# M224X.net
KiCad netlist of a schematic drawn in EAGLE
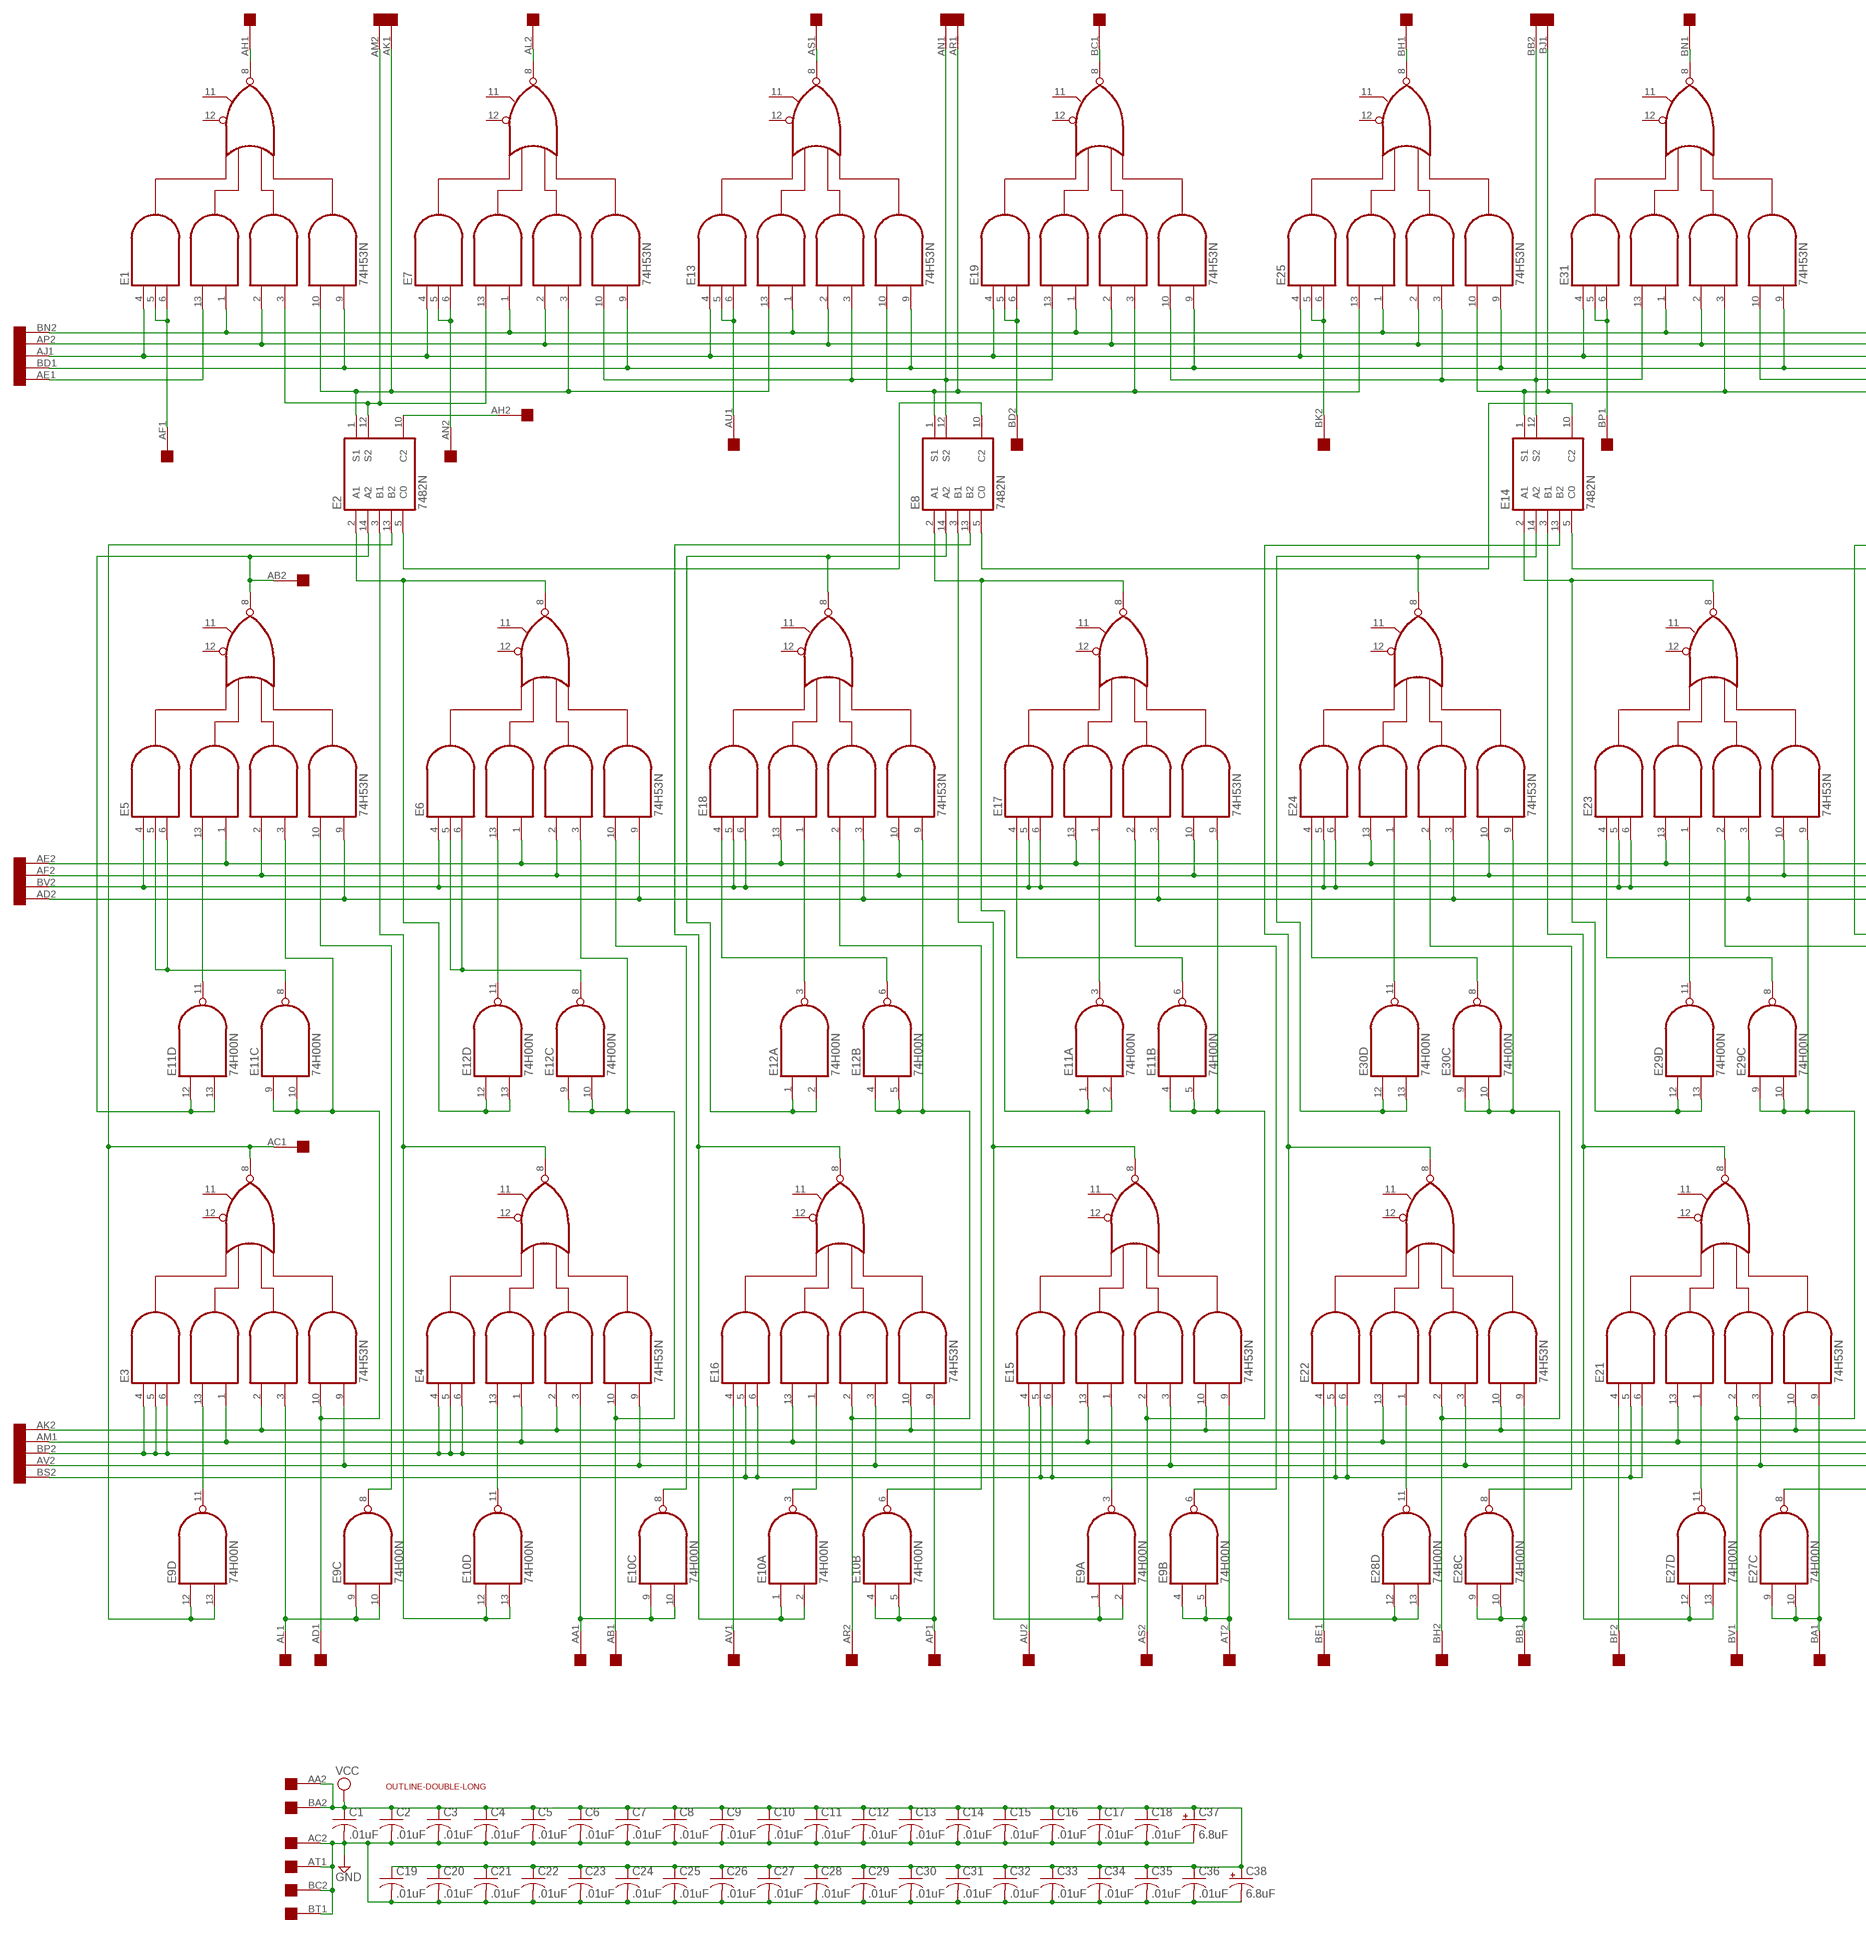
[diagram p0: schematic, sheet 1, part 1 of 2]
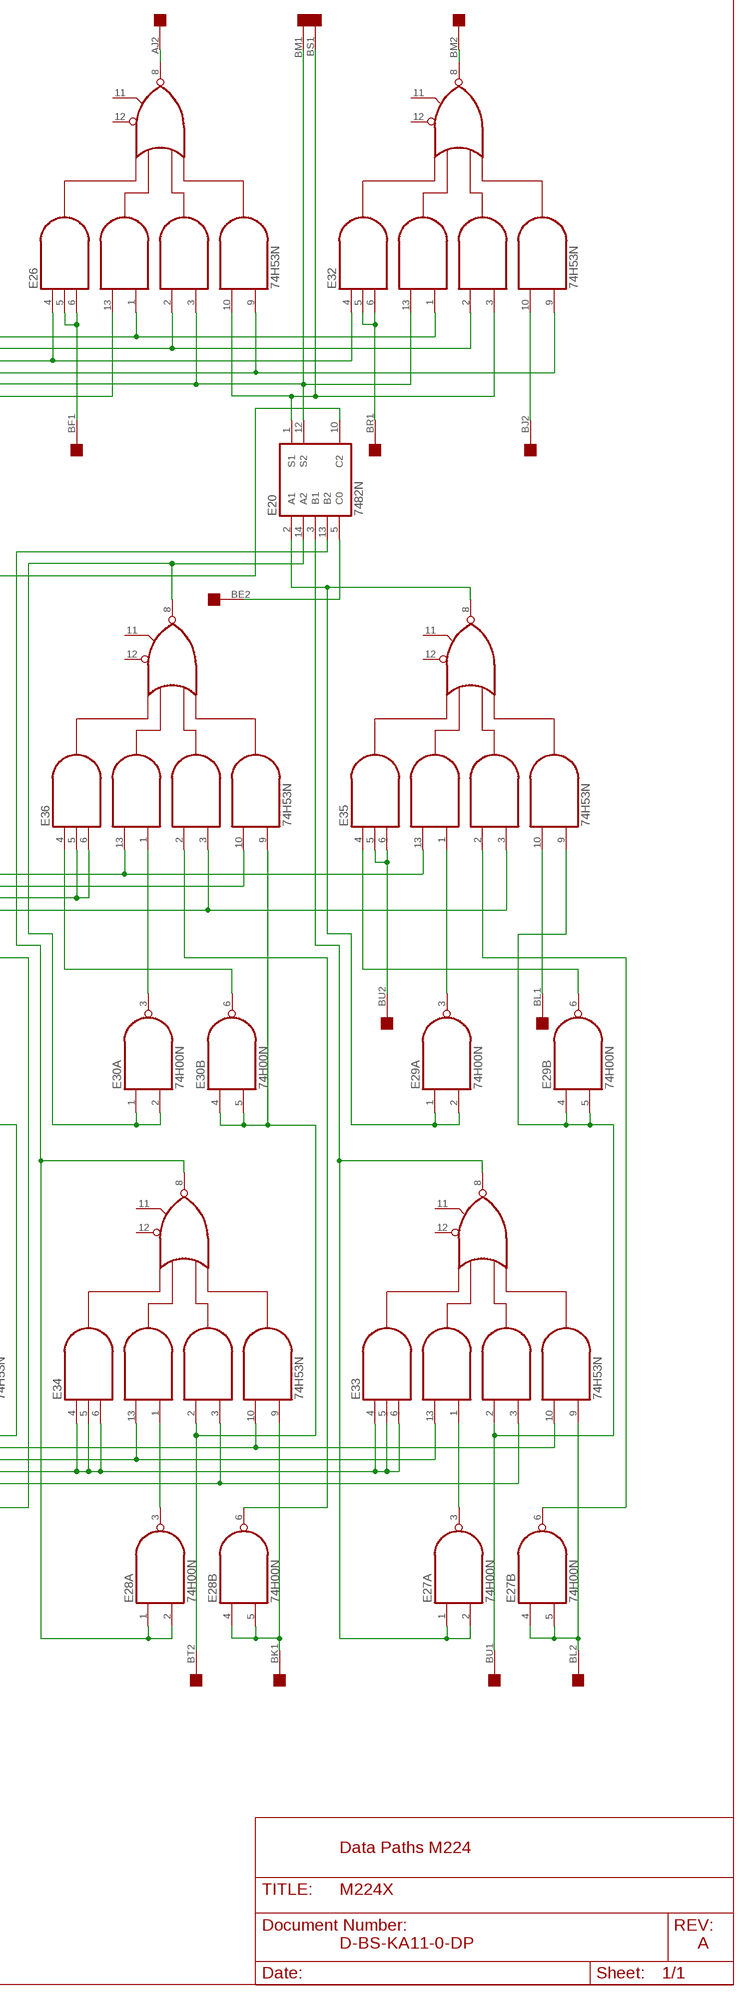
[diagram p1: schematic, sheet 1, part 2 of 2]

(export (version "E")
  (design (tool "Eeschema 10.0.6"))
  (components
    (comp (ref "C1")
      (value ".01uF")
      (footprint "eagle-import:C050-025X075")
      (libsource (lib "eagle-import") (part "C-US050-025X075"))
    )
    (comp (ref "C2")
      (value ".01uF")
      (footprint "eagle-import:C050-025X075")
      (libsource (lib "eagle-import") (part "C-US050-025X075"))
    )
    (comp (ref "C3")
      (value ".01uF")
      (footprint "eagle-import:C050-025X075")
      (libsource (lib "eagle-import") (part "C-US050-025X075"))
    )
    (comp (ref "C4")
      (value ".01uF")
      (footprint "eagle-import:C050-025X075")
      (libsource (lib "eagle-import") (part "C-US050-025X075"))
    )
    (comp (ref "C5")
      (value ".01uF")
      (footprint "eagle-import:C050-025X075")
      (libsource (lib "eagle-import") (part "C-US050-025X075"))
    )
    (comp (ref "C6")
      (value ".01uF")
      (footprint "eagle-import:C050-025X075")
      (libsource (lib "eagle-import") (part "C-US050-025X075"))
    )
    (comp (ref "C7")
      (value ".01uF")
      (footprint "eagle-import:C050-025X075")
      (libsource (lib "eagle-import") (part "C-US050-025X075"))
    )
    (comp (ref "C8")
      (value ".01uF")
      (footprint "eagle-import:C050-025X075")
      (libsource (lib "eagle-import") (part "C-US050-025X075"))
    )
    (comp (ref "C9")
      (value ".01uF")
      (footprint "eagle-import:C050-025X075")
      (libsource (lib "eagle-import") (part "C-US050-025X075"))
    )
    (comp (ref "C10")
      (value ".01uF")
      (footprint "eagle-import:C050-025X075")
      (libsource (lib "eagle-import") (part "C-US050-025X075"))
    )
    (comp (ref "C11")
      (value ".01uF")
      (footprint "eagle-import:C050-025X075")
      (libsource (lib "eagle-import") (part "C-US050-025X075"))
    )
    (comp (ref "C12")
      (value ".01uF")
      (footprint "eagle-import:C050-025X075")
      (libsource (lib "eagle-import") (part "C-US050-025X075"))
    )
    (comp (ref "C13")
      (value ".01uF")
      (footprint "eagle-import:C050-025X075")
      (libsource (lib "eagle-import") (part "C-US050-025X075"))
    )
    (comp (ref "C14")
      (value ".01uF")
      (footprint "eagle-import:C050-025X075")
      (libsource (lib "eagle-import") (part "C-US050-025X075"))
    )
    (comp (ref "C15")
      (value ".01uF")
      (footprint "eagle-import:C050-025X075")
      (libsource (lib "eagle-import") (part "C-US050-025X075"))
    )
    (comp (ref "C16")
      (value ".01uF")
      (footprint "eagle-import:C050-025X075")
      (libsource (lib "eagle-import") (part "C-US050-025X075"))
    )
    (comp (ref "C17")
      (value ".01uF")
      (footprint "eagle-import:C050-025X075")
      (libsource (lib "eagle-import") (part "C-US050-025X075"))
    )
    (comp (ref "C18")
      (value ".01uF")
      (footprint "eagle-import:C050-025X075")
      (libsource (lib "eagle-import") (part "C-US050-025X075"))
    )
    (comp (ref "C19")
      (value ".01uF")
      (footprint "eagle-import:C050-025X075")
      (libsource (lib "eagle-import") (part "C-US050-025X075"))
    )
    (comp (ref "C20")
      (value ".01uF")
      (footprint "eagle-import:C050-025X075")
      (libsource (lib "eagle-import") (part "C-US050-025X075"))
    )
    (comp (ref "C21")
      (value ".01uF")
      (footprint "eagle-import:C050-025X075")
      (libsource (lib "eagle-import") (part "C-US050-025X075"))
    )
    (comp (ref "C22")
      (value ".01uF")
      (footprint "eagle-import:C050-025X075")
      (libsource (lib "eagle-import") (part "C-US050-025X075"))
    )
    (comp (ref "C23")
      (value ".01uF")
      (footprint "eagle-import:C050-025X075")
      (libsource (lib "eagle-import") (part "C-US050-025X075"))
    )
    (comp (ref "C24")
      (value ".01uF")
      (footprint "eagle-import:C050-025X075")
      (libsource (lib "eagle-import") (part "C-US050-025X075"))
    )
    (comp (ref "C25")
      (value ".01uF")
      (footprint "eagle-import:C050-025X075")
      (libsource (lib "eagle-import") (part "C-US050-025X075"))
    )
    (comp (ref "C26")
      (value ".01uF")
      (footprint "eagle-import:C050-025X075")
      (libsource (lib "eagle-import") (part "C-US050-025X075"))
    )
    (comp (ref "C27")
      (value ".01uF")
      (footprint "eagle-import:C050-025X075")
      (libsource (lib "eagle-import") (part "C-US050-025X075"))
    )
    (comp (ref "C28")
      (value ".01uF")
      (footprint "eagle-import:C050-025X075")
      (libsource (lib "eagle-import") (part "C-US050-025X075"))
    )
    (comp (ref "C29")
      (value ".01uF")
      (footprint "eagle-import:C050-025X075")
      (libsource (lib "eagle-import") (part "C-US050-025X075"))
    )
    (comp (ref "C30")
      (value ".01uF")
      (footprint "eagle-import:C050-025X075")
      (libsource (lib "eagle-import") (part "C-US050-025X075"))
    )
    (comp (ref "C31")
      (value ".01uF")
      (footprint "eagle-import:C050-025X075")
      (libsource (lib "eagle-import") (part "C-US050-025X075"))
    )
    (comp (ref "C32")
      (value ".01uF")
      (footprint "eagle-import:C050-025X075")
      (libsource (lib "eagle-import") (part "C-US050-025X075"))
    )
    (comp (ref "C33")
      (value ".01uF")
      (footprint "eagle-import:C050-025X075")
      (libsource (lib "eagle-import") (part "C-US050-025X075"))
    )
    (comp (ref "C34")
      (value ".01uF")
      (footprint "eagle-import:C050-025X075")
      (libsource (lib "eagle-import") (part "C-US050-025X075"))
    )
    (comp (ref "C35")
      (value ".01uF")
      (footprint "eagle-import:C050-025X075")
      (libsource (lib "eagle-import") (part "C-US050-025X075"))
    )
    (comp (ref "C36")
      (value ".01uF")
      (footprint "eagle-import:C050-025X075")
      (libsource (lib "eagle-import") (part "C-US050-025X075"))
    )
    (comp (ref "C37")
      (value "6.8uF")
      (footprint "eagle-import:E12-8")
      (libsource (lib "eagle-import") (part "CPOL-USE20-8AXIAL"))
    )
    (comp (ref "C38")
      (value "6.8uF")
      (footprint "eagle-import:E12-8")
      (libsource (lib "eagle-import") (part "CPOL-USE20-8AXIAL"))
    )
    (comp (ref "E1")
      (value "74H53N")
      (footprint "eagle-import:DIL14")
      (libsource (lib "eagle-import") (part "74H53N"))
    )
    (comp (ref "E2")
      (value "7482N")
      (footprint "eagle-import:DIL14")
      (libsource (lib "eagle-import") (part "7482N"))
    )
    (comp (ref "E3")
      (value "74H53N")
      (footprint "eagle-import:DIL14")
      (libsource (lib "eagle-import") (part "74H53N"))
    )
    (comp (ref "E4")
      (value "74H53N")
      (footprint "eagle-import:DIL14")
      (libsource (lib "eagle-import") (part "74H53N"))
    )
    (comp (ref "E5")
      (value "74H53N")
      (footprint "eagle-import:DIL14")
      (libsource (lib "eagle-import") (part "74H53N"))
    )
    (comp (ref "E6")
      (value "74H53N")
      (footprint "eagle-import:DIL14")
      (libsource (lib "eagle-import") (part "74H53N"))
    )
    (comp (ref "E7")
      (value "74H53N")
      (footprint "eagle-import:DIL14")
      (libsource (lib "eagle-import") (part "74H53N"))
    )
    (comp (ref "E8")
      (value "7482N")
      (footprint "eagle-import:DIL14")
      (libsource (lib "eagle-import") (part "7482N"))
    )
    (comp (ref "E9")
      (value "74H00N")
      (footprint "eagle-import:DIL14")
      (libsource (lib "eagle-import") (part "7400NS"))
    )
    (comp (ref "E10")
      (value "74H00N")
      (footprint "eagle-import:DIL14")
      (libsource (lib "eagle-import") (part "7400NS"))
    )
    (comp (ref "E11")
      (value "74H00N")
      (footprint "eagle-import:DIL14")
      (libsource (lib "eagle-import") (part "7400NS"))
    )
    (comp (ref "E12")
      (value "74H00N")
      (footprint "eagle-import:DIL14")
      (libsource (lib "eagle-import") (part "7400NS"))
    )
    (comp (ref "E13")
      (value "74H53N")
      (footprint "eagle-import:DIL14")
      (libsource (lib "eagle-import") (part "74H53N"))
    )
    (comp (ref "E14")
      (value "7482N")
      (footprint "eagle-import:DIL14")
      (libsource (lib "eagle-import") (part "7482N"))
    )
    (comp (ref "E15")
      (value "74H53N")
      (footprint "eagle-import:DIL14")
      (libsource (lib "eagle-import") (part "74H53N"))
    )
    (comp (ref "E16")
      (value "74H53N")
      (footprint "eagle-import:DIL14")
      (libsource (lib "eagle-import") (part "74H53N"))
    )
    (comp (ref "E17")
      (value "74H53N")
      (footprint "eagle-import:DIL14")
      (libsource (lib "eagle-import") (part "74H53N"))
    )
    (comp (ref "E18")
      (value "74H53N")
      (footprint "eagle-import:DIL14")
      (libsource (lib "eagle-import") (part "74H53N"))
    )
    (comp (ref "E19")
      (value "74H53N")
      (footprint "eagle-import:DIL14")
      (libsource (lib "eagle-import") (part "74H53N"))
    )
    (comp (ref "E20")
      (value "7482N")
      (footprint "eagle-import:DIL14")
      (libsource (lib "eagle-import") (part "7482N"))
    )
    (comp (ref "E21")
      (value "74H53N")
      (footprint "eagle-import:DIL14")
      (libsource (lib "eagle-import") (part "74H53N"))
    )
    (comp (ref "E22")
      (value "74H53N")
      (footprint "eagle-import:DIL14")
      (libsource (lib "eagle-import") (part "74H53N"))
    )
    (comp (ref "E23")
      (value "74H53N")
      (footprint "eagle-import:DIL14")
      (libsource (lib "eagle-import") (part "74H53N"))
    )
    (comp (ref "E24")
      (value "74H53N")
      (footprint "eagle-import:DIL14")
      (libsource (lib "eagle-import") (part "74H53N"))
    )
    (comp (ref "E25")
      (value "74H53N")
      (footprint "eagle-import:DIL14")
      (libsource (lib "eagle-import") (part "74H53N"))
    )
    (comp (ref "E26")
      (value "74H53N")
      (footprint "eagle-import:DIL14")
      (libsource (lib "eagle-import") (part "74H53N"))
    )
    (comp (ref "E27")
      (value "74H00N")
      (footprint "eagle-import:DIL14")
      (libsource (lib "eagle-import") (part "7400NS"))
    )
    (comp (ref "E28")
      (value "74H00N")
      (footprint "eagle-import:DIL14")
      (libsource (lib "eagle-import") (part "7400NS"))
    )
    (comp (ref "E29")
      (value "74H00N")
      (footprint "eagle-import:DIL14")
      (libsource (lib "eagle-import") (part "7400NS"))
    )
    (comp (ref "E30")
      (value "74H00N")
      (footprint "eagle-import:DIL14")
      (libsource (lib "eagle-import") (part "7400NS"))
    )
    (comp (ref "E31")
      (value "74H53N")
      (footprint "eagle-import:DIL14")
      (libsource (lib "eagle-import") (part "74H53N"))
    )
    (comp (ref "E32")
      (value "74H53N")
      (footprint "eagle-import:DIL14")
      (libsource (lib "eagle-import") (part "74H53N"))
    )
    (comp (ref "E33")
      (value "74H53N")
      (footprint "eagle-import:DIL14")
      (libsource (lib "eagle-import") (part "74H53N"))
    )
    (comp (ref "E34")
      (value "74H53N")
      (footprint "eagle-import:DIL14")
      (libsource (lib "eagle-import") (part "74H53N"))
    )
    (comp (ref "E35")
      (value "74H53N")
      (footprint "eagle-import:DIL14")
      (libsource (lib "eagle-import") (part "74H53N"))
    )
    (comp (ref "E36")
      (value "74H53N")
      (footprint "eagle-import:DIL14")
      (libsource (lib "eagle-import") (part "74H53N"))
    )
    (comp (ref "U$1")
      (value "OUTLINE-DOUBLE-LONG")
      (footprint "eagle-import:DOUBLE-LONG")
      (libsource (lib "eagle-import") (part "OUTLINE-DOUBLE-LONG"))
    )
    (comp (ref "U$3")
      (value "DOUBLE")
      (footprint "eagle-import:EDGE-CON4")
      (libsource (lib "eagle-import") (part "DOUBLE"))
    )
  )
  (nets
    (net (code "1") (name "GND") (class "Default")
      (node (ref "C1") (pin "2") (pinfunction "2_2") (pintype "passive"))
      (node (ref "C10") (pin "2") (pinfunction "2_2") (pintype "passive"))
      (node (ref "C11") (pin "2") (pinfunction "2_2") (pintype "passive"))
      (node (ref "C12") (pin "2") (pinfunction "2_2") (pintype "passive"))
      (node (ref "C13") (pin "2") (pinfunction "2_2") (pintype "passive"))
      (node (ref "C14") (pin "2") (pinfunction "2_2") (pintype "passive"))
      (node (ref "C15") (pin "2") (pinfunction "2_2") (pintype "passive"))
      (node (ref "C16") (pin "2") (pinfunction "2_2") (pintype "passive"))
      (node (ref "C17") (pin "2") (pinfunction "2_2") (pintype "passive"))
      (node (ref "C18") (pin "2") (pinfunction "2_2") (pintype "passive"))
      (node (ref "C19") (pin "2") (pinfunction "2_2") (pintype "passive"))
      (node (ref "C2") (pin "2") (pinfunction "2_2") (pintype "passive"))
      (node (ref "C20") (pin "2") (pinfunction "2_2") (pintype "passive"))
      (node (ref "C21") (pin "2") (pinfunction "2_2") (pintype "passive"))
      (node (ref "C22") (pin "2") (pinfunction "2_2") (pintype "passive"))
      (node (ref "C23") (pin "2") (pinfunction "2_2") (pintype "passive"))
      (node (ref "C24") (pin "2") (pinfunction "2_2") (pintype "passive"))
      (node (ref "C25") (pin "2") (pinfunction "2_2") (pintype "passive"))
      (node (ref "C26") (pin "2") (pinfunction "2_2") (pintype "passive"))
      (node (ref "C27") (pin "2") (pinfunction "2_2") (pintype "passive"))
      (node (ref "C28") (pin "2") (pinfunction "2_2") (pintype "passive"))
      (node (ref "C29") (pin "2") (pinfunction "2_2") (pintype "passive"))
      (node (ref "C3") (pin "2") (pinfunction "2_2") (pintype "passive"))
      (node (ref "C30") (pin "2") (pinfunction "2_2") (pintype "passive"))
      (node (ref "C31") (pin "2") (pinfunction "2_2") (pintype "passive"))
      (node (ref "C32") (pin "2") (pinfunction "2_2") (pintype "passive"))
      (node (ref "C33") (pin "2") (pinfunction "2_2") (pintype "passive"))
      (node (ref "C34") (pin "2") (pinfunction "2_2") (pintype "passive"))
      (node (ref "C35") (pin "2") (pinfunction "2_2") (pintype "passive"))
      (node (ref "C36") (pin "2") (pinfunction "2_2") (pintype "passive"))
      (node (ref "C37") (pin "-") (pinfunction "-_-") (pintype "passive"))
      (node (ref "C38") (pin "-") (pinfunction "-_-") (pintype "passive"))
      (node (ref "C4") (pin "2") (pinfunction "2_2") (pintype "passive"))
      (node (ref "C5") (pin "2") (pinfunction "2_2") (pintype "passive"))
      (node (ref "C6") (pin "2") (pinfunction "2_2") (pintype "passive"))
      (node (ref "C7") (pin "2") (pinfunction "2_2") (pintype "passive"))
      (node (ref "C8") (pin "2") (pinfunction "2_2") (pintype "passive"))
      (node (ref "C9") (pin "2") (pinfunction "2_2") (pintype "passive"))
      (node (ref "U$3") (pin "AC2") (pinfunction "1_AC2") (pintype "bidirectional"))
      (node (ref "U$3") (pin "AT1") (pinfunction "1_AT1") (pintype "bidirectional"))
      (node (ref "U$3") (pin "BC2") (pinfunction "1_BC2") (pintype "bidirectional"))
      (node (ref "U$3") (pin "BT1") (pinfunction "1_BT1") (pintype "bidirectional"))
    )
    (net (code "2") (name "Net-(E1A-I3)") (class "Default")
      (node (ref "E1") (pin "13") (pinfunction "I3_13") (pintype "input"))
      (node (ref "U$3") (pin "AE1") (pinfunction "1_AE1") (pintype "bidirectional"))
    )
    (net (code "3") (name "Net-(E1A-I6)") (class "Default")
      (node (ref "E1") (pin "3") (pinfunction "I6_3") (pintype "input"))
      (node (ref "E2") (pin "12") (pinfunction "S2_12") (pintype "output"))
      (node (ref "E7") (pin "13") (pinfunction "I3_13") (pintype "input"))
      (node (ref "U$3") (pin "AM2") (pinfunction "1_AM2") (pintype "bidirectional"))
    )
    (net (code "4") (name "Net-(E1A-I11)") (class "Default")
      (node (ref "E1") (pin "5") (pinfunction "I11_5") (pintype "input"))
      (node (ref "E1") (pin "6") (pinfunction "I2_6") (pintype "input"))
      (node (ref "U$3") (pin "AF1") (pinfunction "1_AF1") (pintype "bidirectional"))
    )
    (net (code "5") (name "Net-(E1A-O)") (class "Default")
      (node (ref "E1") (pin "8") (pinfunction "O_8") (pintype "output"))
      (node (ref "U$3") (pin "AH1") (pinfunction "1_AH1") (pintype "bidirectional"))
    )
    (net (code "6") (name "Net-(E2E-B2)") (class "Default")
      (node (ref "E2") (pin "13") (pinfunction "B2_13") (pintype "input"))
      (node (ref "E3") (pin "8") (pinfunction "O_8") (pintype "output"))
      (node (ref "E9") (pin "12") (pinfunction "I0_12") (pintype "input"))
      (node (ref "E9") (pin "13") (pinfunction "I1_13") (pintype "input"))
      (node (ref "U$3") (pin "AC1") (pinfunction "1_AC1") (pintype "bidirectional"))
    )
    (net (code "7") (name "Net-(E2E-C0)") (class "Default")
      (node (ref "E2") (pin "5") (pinfunction "C0_5") (pintype "input"))
      (node (ref "E8") (pin "10") (pinfunction "C2_10") (pintype "output"))
    )
    (net (code "8") (name "Net-(E2E-C2)") (class "Default")
      (node (ref "E2") (pin "10") (pinfunction "C2_10") (pintype "output"))
      (node (ref "U$3") (pin "AH2") (pinfunction "1_AH2") (pintype "bidirectional"))
    )
    (net (code "9") (name "Net-(E3A-I3)") (class "Default")
      (node (ref "E3") (pin "13") (pinfunction "I3_13") (pintype "input"))
      (node (ref "E9") (pin "11") (pinfunction "O_11") (pintype "output"))
    )
    (net (code "10") (name "Net-(E3A-I6)") (class "Default")
      (node (ref "E3") (pin "3") (pinfunction "I6_3") (pintype "input"))
      (node (ref "E9") (pin "10") (pinfunction "I1_10") (pintype "input"))
      (node (ref "E9") (pin "9") (pinfunction "I0_9") (pintype "input"))
      (node (ref "U$3") (pin "AL1") (pinfunction "1_AL1") (pintype "bidirectional"))
    )
    (net (code "11") (name "Net-(E5A-I7)") (class "Default")
      (node (ref "E5") (pin "10") (pinfunction "I7_10") (pintype "input"))
      (node (ref "E9") (pin "8") (pinfunction "O_8") (pintype "output"))
    )
    (net (code "12") (name "Net-(E7A-I11)") (class "Default")
      (node (ref "E7") (pin "5") (pinfunction "I11_5") (pintype "input"))
      (node (ref "E7") (pin "6") (pinfunction "I2_6") (pintype "input"))
      (node (ref "U$3") (pin "AN2") (pinfunction "1_AN2") (pintype "bidirectional"))
    )
    (net (code "13") (name "Net-(E7A-O)") (class "Default")
      (node (ref "E7") (pin "8") (pinfunction "O_8") (pintype "output"))
      (node (ref "U$3") (pin "AL2") (pinfunction "1_AL2") (pintype "bidirectional"))
    )
    (net (code "14") (name "Net-(E10A-I0)") (class "Default")
      (node (ref "E10") (pin "1") (pinfunction "I0_1") (pintype "input"))
      (node (ref "E10") (pin "2") (pinfunction "I1_2") (pintype "input"))
      (node (ref "E16") (pin "8") (pinfunction "O_8") (pintype "output"))
      (node (ref "E8") (pin "13") (pinfunction "B2_13") (pintype "input"))
    )
    (net (code "15") (name "Net-(E10A-O)") (class "Default")
      (node (ref "E10") (pin "3") (pinfunction "O_3") (pintype "output"))
      (node (ref "E16") (pin "1") (pinfunction "I4_1") (pintype "input"))
    )
    (net (code "16") (name "Net-(E10B-I0)") (class "Default")
      (node (ref "E10") (pin "4") (pinfunction "I0_4") (pintype "input"))
      (node (ref "E10") (pin "5") (pinfunction "I1_5") (pintype "input"))
      (node (ref "E16") (pin "9") (pinfunction "I8_9") (pintype "input"))
      (node (ref "U$3") (pin "AP1") (pinfunction "1_AP1") (pintype "bidirectional"))
    )
    (net (code "17") (name "Net-(E10B-O)") (class "Default")
      (node (ref "E10") (pin "6") (pinfunction "O_6") (pintype "output"))
      (node (ref "E18") (pin "2") (pinfunction "I5_2") (pintype "input"))
    )
    (net (code "18") (name "Net-(E10C-I0)") (class "Default")
      (node (ref "E10") (pin "10") (pinfunction "I1_10") (pintype "input"))
      (node (ref "E10") (pin "9") (pinfunction "I0_9") (pintype "input"))
      (node (ref "E4") (pin "3") (pinfunction "I6_3") (pintype "input"))
      (node (ref "U$3") (pin "AA1") (pinfunction "1_AA1") (pintype "bidirectional"))
    )
    (net (code "19") (name "Net-(E10C-O)") (class "Default")
      (node (ref "E10") (pin "8") (pinfunction "O_8") (pintype "output"))
      (node (ref "E6") (pin "10") (pinfunction "I7_10") (pintype "input"))
    )
    (net (code "20") (name "Net-(E10D-I0)") (class "Default")
      (node (ref "E10") (pin "12") (pinfunction "I0_12") (pintype "input"))
      (node (ref "E10") (pin "13") (pinfunction "I1_13") (pintype "input"))
      (node (ref "E2") (pin "3") (pinfunction "B1_3") (pintype "input"))
      (node (ref "E4") (pin "8") (pinfunction "O_8") (pintype "output"))
    )
    (net (code "21") (name "Net-(E10D-O)") (class "Default")
      (node (ref "E10") (pin "11") (pinfunction "O_11") (pintype "output"))
      (node (ref "E4") (pin "13") (pinfunction "I3_13") (pintype "input"))
    )
    (net (code "22") (name "Net-(E11A-I0)") (class "Default")
      (node (ref "E11") (pin "1") (pinfunction "I0_1") (pintype "input"))
      (node (ref "E11") (pin "2") (pinfunction "I1_2") (pintype "input"))
      (node (ref "E17") (pin "8") (pinfunction "O_8") (pintype "output"))
      (node (ref "E8") (pin "2") (pinfunction "A1_2") (pintype "input"))
    )
    (net (code "23") (name "Net-(E11A-O)") (class "Default")
      (node (ref "E11") (pin "3") (pinfunction "O_3") (pintype "output"))
      (node (ref "E17") (pin "1") (pinfunction "I4_1") (pintype "input"))
    )
    (net (code "24") (name "Net-(E11B-I0)") (class "Default")
      (node (ref "E11") (pin "4") (pinfunction "I0_4") (pintype "input"))
      (node (ref "E11") (pin "5") (pinfunction "I1_5") (pintype "input"))
      (node (ref "E15") (pin "2") (pinfunction "I5_2") (pintype "input"))
      (node (ref "E17") (pin "9") (pinfunction "I8_9") (pintype "input"))
      (node (ref "U$3") (pin "AS2") (pinfunction "1_AS2") (pintype "bidirectional"))
    )
    (net (code "25") (name "Net-(E11B-O)") (class "Default")
      (node (ref "E11") (pin "6") (pinfunction "O_6") (pintype "output"))
      (node (ref "E17") (pin "4") (pinfunction "I1_4") (pintype "input"))
    )
    (net (code "26") (name "Net-(E11C-I0)") (class "Default")
      (node (ref "E11") (pin "10") (pinfunction "I1_10") (pintype "input"))
      (node (ref "E11") (pin "9") (pinfunction "I0_9") (pintype "input"))
      (node (ref "E3") (pin "10") (pinfunction "I7_10") (pintype "input"))
      (node (ref "E5") (pin "3") (pinfunction "I6_3") (pintype "input"))
      (node (ref "U$3") (pin "AD1") (pinfunction "1_AD1") (pintype "bidirectional"))
    )
    (net (code "27") (name "Net-(E11C-O)") (class "Default")
      (node (ref "E11") (pin "8") (pinfunction "O_8") (pintype "output"))
      (node (ref "E5") (pin "5") (pinfunction "I11_5") (pintype "input"))
      (node (ref "E5") (pin "6") (pinfunction "I2_6") (pintype "input"))
    )
    (net (code "28") (name "Net-(E11D-I0)") (class "Default")
      (node (ref "E11") (pin "12") (pinfunction "I0_12") (pintype "input"))
      (node (ref "E11") (pin "13") (pinfunction "I1_13") (pintype "input"))
      (node (ref "E2") (pin "14") (pinfunction "A2_14") (pintype "input"))
      (node (ref "E5") (pin "8") (pinfunction "O_8") (pintype "output"))
      (node (ref "U$3") (pin "AB2") (pinfunction "1_AB2") (pintype "bidirectional"))
    )
    (net (code "29") (name "Net-(E11D-O)") (class "Default")
      (node (ref "E11") (pin "11") (pinfunction "O_11") (pintype "output"))
      (node (ref "E5") (pin "13") (pinfunction "I3_13") (pintype "input"))
    )
    (net (code "30") (name "Net-(E12A-I0)") (class "Default")
      (node (ref "E12") (pin "1") (pinfunction "I0_1") (pintype "input"))
      (node (ref "E12") (pin "2") (pinfunction "I1_2") (pintype "input"))
      (node (ref "E18") (pin "8") (pinfunction "O_8") (pintype "output"))
      (node (ref "E8") (pin "14") (pinfunction "A2_14") (pintype "input"))
    )
    (net (code "31") (name "Net-(E12A-O)") (class "Default")
      (node (ref "E12") (pin "3") (pinfunction "O_3") (pintype "output"))
      (node (ref "E18") (pin "1") (pinfunction "I4_1") (pintype "input"))
    )
    (net (code "32") (name "Net-(E12B-I0)") (class "Default")
      (node (ref "E12") (pin "4") (pinfunction "I0_4") (pintype "input"))
      (node (ref "E12") (pin "5") (pinfunction "I1_5") (pintype "input"))
      (node (ref "E16") (pin "2") (pinfunction "I5_2") (pintype "input"))
      (node (ref "E18") (pin "9") (pinfunction "I8_9") (pintype "input"))
      (node (ref "U$3") (pin "AR2") (pinfunction "1_AR2") (pintype "bidirectional"))
    )
    (net (code "33") (name "Net-(E12B-O)") (class "Default")
      (node (ref "E12") (pin "6") (pinfunction "O_6") (pintype "output"))
      (node (ref "E18") (pin "4") (pinfunction "I1_4") (pintype "input"))
    )
    (net (code "34") (name "Net-(E12C-I0)") (class "Default")
      (node (ref "E12") (pin "10") (pinfunction "I1_10") (pintype "input"))
      (node (ref "E12") (pin "9") (pinfunction "I0_9") (pintype "input"))
      (node (ref "E4") (pin "10") (pinfunction "I7_10") (pintype "input"))
      (node (ref "E6") (pin "3") (pinfunction "I6_3") (pintype "input"))
      (node (ref "U$3") (pin "AB1") (pinfunction "1_AB1") (pintype "bidirectional"))
    )
    (net (code "35") (name "Net-(E12C-O)") (class "Default")
      (node (ref "E12") (pin "8") (pinfunction "O_8") (pintype "output"))
      (node (ref "E6") (pin "5") (pinfunction "I11_5") (pintype "input"))
      (node (ref "E6") (pin "6") (pinfunction "I2_6") (pintype "input"))
    )
    (net (code "36") (name "Net-(E12D-I0)") (class "Default")
      (node (ref "E12") (pin "12") (pinfunction "I0_12") (pintype "input"))
      (node (ref "E12") (pin "13") (pinfunction "I1_13") (pintype "input"))
      (node (ref "E2") (pin "2") (pinfunction "A1_2") (pintype "input"))
      (node (ref "E6") (pin "8") (pinfunction "O_8") (pintype "output"))
    )
    (net (code "37") (name "Net-(E12D-O)") (class "Default")
      (node (ref "E12") (pin "11") (pinfunction "O_11") (pintype "output"))
      (node (ref "E6") (pin "13") (pinfunction "I3_13") (pintype "input"))
    )
    (net (code "38") (name "Net-(E13A-I1)") (class "Default")
      (node (ref "E1") (pin "4") (pinfunction "I1_4") (pintype "input"))
      (node (ref "E13") (pin "4") (pinfunction "I1_4") (pintype "input"))
      (node (ref "E19") (pin "4") (pinfunction "I1_4") (pintype "input"))
      (node (ref "E25") (pin "4") (pinfunction "I1_4") (pintype "input"))
      (node (ref "E26") (pin "4") (pinfunction "I1_4") (pintype "input"))
      (node (ref "E31") (pin "4") (pinfunction "I1_4") (pintype "input"))
      (node (ref "E32") (pin "4") (pinfunction "I1_4") (pintype "input"))
      (node (ref "E7") (pin "4") (pinfunction "I1_4") (pintype "input"))
      (node (ref "U$3") (pin "AJ1") (pinfunction "1_AJ1") (pintype "bidirectional"))
    )
    (net (code "39") (name "Net-(E13A-I3)") (class "Default")
      (node (ref "E1") (pin "10") (pinfunction "I7_10") (pintype "input"))
      (node (ref "E13") (pin "13") (pinfunction "I3_13") (pintype "input"))
      (node (ref "E2") (pin "1") (pinfunction "S1_1") (pintype "output"))
      (node (ref "E7") (pin "3") (pinfunction "I6_3") (pintype "input"))
      (node (ref "U$3") (pin "AK1") (pinfunction "1_AK1") (pintype "bidirectional"))
    )
    (net (code "40") (name "Net-(E13A-I4)") (class "Default")
      (node (ref "E1") (pin "1") (pinfunction "I4_1") (pintype "input"))
      (node (ref "E13") (pin "1") (pinfunction "I4_1") (pintype "input"))
      (node (ref "E19") (pin "1") (pinfunction "I4_1") (pintype "input"))
      (node (ref "E25") (pin "1") (pinfunction "I4_1") (pintype "input"))
      (node (ref "E26") (pin "1") (pinfunction "I4_1") (pintype "input"))
      (node (ref "E31") (pin "1") (pinfunction "I4_1") (pintype "input"))
      (node (ref "E32") (pin "1") (pinfunction "I4_1") (pintype "input"))
      (node (ref "E7") (pin "1") (pinfunction "I4_1") (pintype "input"))
      (node (ref "U$3") (pin "BN2") (pinfunction "1_BN2") (pintype "bidirectional"))
    )
    (net (code "41") (name "Net-(E13A-I5)") (class "Default")
      (node (ref "E1") (pin "2") (pinfunction "I5_2") (pintype "input"))
      (node (ref "E13") (pin "2") (pinfunction "I5_2") (pintype "input"))
      (node (ref "E19") (pin "2") (pinfunction "I5_2") (pintype "input"))
      (node (ref "E25") (pin "2") (pinfunction "I5_2") (pintype "input"))
      (node (ref "E26") (pin "2") (pinfunction "I5_2") (pintype "input"))
      (node (ref "E31") (pin "2") (pinfunction "I5_2") (pintype "input"))
      (node (ref "E32") (pin "2") (pinfunction "I5_2") (pintype "input"))
      (node (ref "E7") (pin "2") (pinfunction "I5_2") (pintype "input"))
      (node (ref "U$3") (pin "AP2") (pinfunction "1_AP2") (pintype "bidirectional"))
    )
    (net (code "42") (name "Net-(E13A-I6)") (class "Default")
      (node (ref "E13") (pin "3") (pinfunction "I6_3") (pintype "input"))
      (node (ref "E19") (pin "13") (pinfunction "I3_13") (pintype "input"))
      (node (ref "E7") (pin "10") (pinfunction "I7_10") (pintype "input"))
      (node (ref "E8") (pin "12") (pinfunction "S2_12") (pintype "output"))
      (node (ref "U$3") (pin "AN1") (pinfunction "1_AN1") (pintype "bidirectional"))
    )
    (net (code "43") (name "Net-(E13A-I7)") (class "Default")
      (node (ref "E13") (pin "10") (pinfunction "I7_10") (pintype "input"))
      (node (ref "E19") (pin "3") (pinfunction "I6_3") (pintype "input"))
      (node (ref "E25") (pin "13") (pinfunction "I3_13") (pintype "input"))
      (node (ref "E8") (pin "1") (pinfunction "S1_1") (pintype "output"))
      (node (ref "U$3") (pin "AR1") (pinfunction "1_AR1") (pintype "bidirectional"))
    )
    (net (code "44") (name "Net-(E13A-I8)") (class "Default")
      (node (ref "E1") (pin "9") (pinfunction "I8_9") (pintype "input"))
      (node (ref "E13") (pin "9") (pinfunction "I8_9") (pintype "input"))
      (node (ref "E19") (pin "9") (pinfunction "I8_9") (pintype "input"))
      (node (ref "E25") (pin "9") (pinfunction "I8_9") (pintype "input"))
      (node (ref "E26") (pin "9") (pinfunction "I8_9") (pintype "input"))
      (node (ref "E31") (pin "9") (pinfunction "I8_9") (pintype "input"))
      (node (ref "E32") (pin "9") (pinfunction "I8_9") (pintype "input"))
      (node (ref "E7") (pin "9") (pinfunction "I8_9") (pintype "input"))
      (node (ref "U$3") (pin "BD1") (pinfunction "1_BD1") (pintype "bidirectional"))
    )
    (net (code "45") (name "Net-(E13A-I11)") (class "Default")
      (node (ref "E13") (pin "5") (pinfunction "I11_5") (pintype "input"))
      (node (ref "E13") (pin "6") (pinfunction "I2_6") (pintype "input"))
      (node (ref "U$3") (pin "AU1") (pinfunction "1_AU1") (pintype "bidirectional"))
    )
    (net (code "46") (name "Net-(E13A-O)") (class "Default")
      (node (ref "E13") (pin "8") (pinfunction "O_8") (pintype "output"))
      (node (ref "U$3") (pin "AS1") (pinfunction "1_AS1") (pintype "bidirectional"))
    )
    (net (code "47") (name "Net-(E14E-A1)") (class "Default")
      (node (ref "E14") (pin "2") (pinfunction "A1_2") (pintype "input"))
      (node (ref "E23") (pin "8") (pinfunction "O_8") (pintype "output"))
      (node (ref "E29") (pin "12") (pinfunction "I0_12") (pintype "input"))
      (node (ref "E29") (pin "13") (pinfunction "I1_13") (pintype "input"))
    )
    (net (code "48") (name "Net-(E14E-A2)") (class "Default")
      (node (ref "E14") (pin "14") (pinfunction "A2_14") (pintype "input"))
      (node (ref "E24") (pin "8") (pinfunction "O_8") (pintype "output"))
      (node (ref "E30") (pin "12") (pinfunction "I0_12") (pintype "input"))
      (node (ref "E30") (pin "13") (pinfunction "I1_13") (pintype "input"))
    )
    (net (code "49") (name "Net-(E14E-B1)") (class "Default")
      (node (ref "E14") (pin "3") (pinfunction "B1_3") (pintype "input"))
      (node (ref "E21") (pin "8") (pinfunction "O_8") (pintype "output"))
      (node (ref "E27") (pin "12") (pinfunction "I0_12") (pintype "input"))
      (node (ref "E27") (pin "13") (pinfunction "I1_13") (pintype "input"))
    )
    (net (code "50") (name "Net-(E14E-B2)") (class "Default")
      (node (ref "E14") (pin "13") (pinfunction "B2_13") (pintype "input"))
      (node (ref "E22") (pin "8") (pinfunction "O_8") (pintype "output"))
      (node (ref "E28") (pin "12") (pinfunction "I0_12") (pintype "input"))
      (node (ref "E28") (pin "13") (pinfunction "I1_13") (pintype "input"))
    )
    (net (code "51") (name "Net-(E14E-C0)") (class "Default")
      (node (ref "E14") (pin "5") (pinfunction "C0_5") (pintype "input"))
      (node (ref "E20") (pin "10") (pinfunction "C2_10") (pintype "output"))
    )
    (net (code "52") (name "Net-(E14E-C2)") (class "Default")
      (node (ref "E14") (pin "10") (pinfunction "C2_10") (pintype "output"))
      (node (ref "E8") (pin "5") (pinfunction "C0_5") (pintype "input"))
    )
    (net (code "53") (name "Net-(E14E-S1)") (class "Default")
      (node (ref "E14") (pin "1") (pinfunction "S1_1") (pintype "output"))
      (node (ref "E25") (pin "10") (pinfunction "I7_10") (pintype "input"))
      (node (ref "E26") (pin "13") (pinfunction "I3_13") (pintype "input"))
      (node (ref "E31") (pin "3") (pinfunction "I6_3") (pintype "input"))
      (node (ref "U$3") (pin "BJ1") (pinfunction "1_BJ1") (pintype "bidirectional"))
    )
    (net (code "54") (name "Net-(E14E-S2)") (class "Default")
      (node (ref "E14") (pin "12") (pinfunction "S2_12") (pintype "output"))
      (node (ref "E19") (pin "10") (pinfunction "I7_10") (pintype "input"))
      (node (ref "E25") (pin "3") (pinfunction "I6_3") (pintype "input"))
      (node (ref "E31") (pin "13") (pinfunction "I3_13") (pintype "input"))
      (node (ref "U$3") (pin "BB2") (pinfunction "1_BB2") (pintype "bidirectional"))
    )
    (net (code "55") (name "Net-(E15A-I1)") (class "Default")
      (node (ref "E15") (pin "4") (pinfunction "I1_4") (pintype "input"))
      (node (ref "U$3") (pin "AU2") (pinfunction "1_AU2") (pintype "bidirectional"))
    )
    (net (code "56") (name "Net-(E15A-I3)") (class "Default")
      (node (ref "E15") (pin "13") (pinfunction "I3_13") (pintype "input"))
      (node (ref "E16") (pin "13") (pinfunction "I3_13") (pintype "input"))
      (node (ref "E21") (pin "13") (pinfunction "I3_13") (pintype "input"))
      (node (ref "E22") (pin "13") (pinfunction "I3_13") (pintype "input"))
      (node (ref "E3") (pin "1") (pinfunction "I4_1") (pintype "input"))
      (node (ref "E33") (pin "13") (pinfunction "I3_13") (pintype "input"))
      (node (ref "E34") (pin "13") (pinfunction "I3_13") (pintype "input"))
      (node (ref "E4") (pin "1") (pinfunction "I4_1") (pintype "input"))
      (node (ref "U$3") (pin "AM1") (pinfunction "1_AM1") (pintype "bidirectional"))
    )
    (net (code "57") (name "Net-(E15A-I4)") (class "Default")
      (node (ref "E15") (pin "1") (pinfunction "I4_1") (pintype "input"))
      (node (ref "E9") (pin "3") (pinfunction "O_3") (pintype "output"))
    )
    (net (code "58") (name "Net-(E15A-I6)") (class "Default")
      (node (ref "E15") (pin "3") (pinfunction "I6_3") (pintype "input"))
      (node (ref "E16") (pin "3") (pinfunction "I6_3") (pintype "input"))
      (node (ref "E21") (pin "3") (pinfunction "I6_3") (pintype "input"))
      (node (ref "E22") (pin "3") (pinfunction "I6_3") (pintype "input"))
      (node (ref "E3") (pin "9") (pinfunction "I8_9") (pintype "input"))
      (node (ref "E33") (pin "3") (pinfunction "I6_3") (pintype "input"))
      (node (ref "E34") (pin "3") (pinfunction "I6_3") (pintype "input"))
      (node (ref "E4") (pin "9") (pinfunction "I8_9") (pintype "input"))
      (node (ref "U$3") (pin "AV2") (pinfunction "1_AV2") (pintype "bidirectional"))
    )
    (net (code "59") (name "Net-(E15A-I7)") (class "Default")
      (node (ref "E15") (pin "10") (pinfunction "I7_10") (pintype "input"))
      (node (ref "E16") (pin "10") (pinfunction "I7_10") (pintype "input"))
      (node (ref "E21") (pin "10") (pinfunction "I7_10") (pintype "input"))
      (node (ref "E22") (pin "10") (pinfunction "I7_10") (pintype "input"))
      (node (ref "E3") (pin "2") (pinfunction "I5_2") (pintype "input"))
      (node (ref "E33") (pin "10") (pinfunction "I7_10") (pintype "input"))
      (node (ref "E34") (pin "10") (pinfunction "I7_10") (pintype "input"))
      (node (ref "E4") (pin "2") (pinfunction "I5_2") (pintype "input"))
      (node (ref "U$3") (pin "AK2") (pinfunction "1_AK2") (pintype "bidirectional"))
    )
    (net (code "60") (name "Net-(E15A-I8)") (class "Default")
      (node (ref "E15") (pin "9") (pinfunction "I8_9") (pintype "input"))
      (node (ref "E9") (pin "4") (pinfunction "I0_4") (pintype "input"))
      (node (ref "E9") (pin "5") (pinfunction "I1_5") (pintype "input"))
      (node (ref "U$3") (pin "AT2") (pinfunction "1_AT2") (pintype "bidirectional"))
    )
    (net (code "61") (name "Net-(E15A-I11)") (class "Default")
      (node (ref "E15") (pin "5") (pinfunction "I11_5") (pintype "input"))
      (node (ref "E15") (pin "6") (pinfunction "I2_6") (pintype "input"))
      (node (ref "E16") (pin "5") (pinfunction "I11_5") (pintype "input"))
      (node (ref "E16") (pin "6") (pinfunction "I2_6") (pintype "input"))
      (node (ref "E21") (pin "5") (pinfunction "I11_5") (pintype "input"))
      (node (ref "E21") (pin "6") (pinfunction "I2_6") (pintype "input"))
      (node (ref "E22") (pin "5") (pinfunction "I11_5") (pintype "input"))
      (node (ref "E22") (pin "6") (pinfunction "I2_6") (pintype "input"))
      (node (ref "U$3") (pin "BS2") (pinfunction "1_BS2") (pintype "bidirectional"))
    )
    (net (code "62") (name "Net-(E15A-O)") (class "Default")
      (node (ref "E15") (pin "8") (pinfunction "O_8") (pintype "output"))
      (node (ref "E8") (pin "3") (pinfunction "B1_3") (pintype "input"))
      (node (ref "E9") (pin "1") (pinfunction "I0_1") (pintype "input"))
      (node (ref "E9") (pin "2") (pinfunction "I1_2") (pintype "input"))
    )
    (net (code "63") (name "Net-(E16A-I1)") (class "Default")
      (node (ref "E16") (pin "4") (pinfunction "I1_4") (pintype "input"))
      (node (ref "U$3") (pin "AV1") (pinfunction "1_AV1") (pintype "bidirectional"))
    )
    (net (code "64") (name "Net-(E17A-I3)") (class "Default")
      (node (ref "E17") (pin "13") (pinfunction "I3_13") (pintype "input"))
      (node (ref "E18") (pin "13") (pinfunction "I3_13") (pintype "input"))
      (node (ref "E23") (pin "13") (pinfunction "I3_13") (pintype "input"))
      (node (ref "E24") (pin "13") (pinfunction "I3_13") (pintype "input"))
      (node (ref "E35") (pin "13") (pinfunction "I3_13") (pintype "input"))
      (node (ref "E36") (pin "13") (pinfunction "I3_13") (pintype "input"))
      (node (ref "E5") (pin "1") (pinfunction "I4_1") (pintype "input"))
      (node (ref "E6") (pin "1") (pinfunction "I4_1") (pintype "input"))
      (node (ref "U$3") (pin "AE2") (pinfunction "1_AE2") (pintype "bidirectional"))
    )
    (net (code "65") (name "Net-(E17A-I5)") (class "Default")
      (node (ref "E17") (pin "2") (pinfunction "I5_2") (pintype "input"))
      (node (ref "E9") (pin "6") (pinfunction "O_6") (pintype "output"))
    )
    (net (code "66") (name "Net-(E17A-I6)") (class "Default")
      (node (ref "E17") (pin "3") (pinfunction "I6_3") (pintype "input"))
      (node (ref "E18") (pin "3") (pinfunction "I6_3") (pintype "input"))
      (node (ref "E23") (pin "3") (pinfunction "I6_3") (pintype "input"))
      (node (ref "E24") (pin "3") (pinfunction "I6_3") (pintype "input"))
      (node (ref "E35") (pin "3") (pinfunction "I6_3") (pintype "input"))
      (node (ref "E36") (pin "3") (pinfunction "I6_3") (pintype "input"))
      (node (ref "E5") (pin "9") (pinfunction "I8_9") (pintype "input"))
      (node (ref "E6") (pin "9") (pinfunction "I8_9") (pintype "input"))
      (node (ref "U$3") (pin "AD2") (pinfunction "1_AD2") (pintype "bidirectional"))
    )
    (net (code "67") (name "Net-(E17A-I7)") (class "Default")
      (node (ref "E17") (pin "10") (pinfunction "I7_10") (pintype "input"))
      (node (ref "E18") (pin "10") (pinfunction "I7_10") (pintype "input"))
      (node (ref "E23") (pin "10") (pinfunction "I7_10") (pintype "input"))
      (node (ref "E24") (pin "10") (pinfunction "I7_10") (pintype "input"))
      (node (ref "E36") (pin "10") (pinfunction "I7_10") (pintype "input"))
      (node (ref "E5") (pin "2") (pinfunction "I5_2") (pintype "input"))
      (node (ref "E6") (pin "2") (pinfunction "I5_2") (pintype "input"))
      (node (ref "U$3") (pin "AF2") (pinfunction "1_AF2") (pintype "bidirectional"))
    )
    (net (code "68") (name "Net-(E17A-I11)") (class "Default")
      (node (ref "E17") (pin "5") (pinfunction "I11_5") (pintype "input"))
      (node (ref "E17") (pin "6") (pinfunction "I2_6") (pintype "input"))
      (node (ref "E18") (pin "5") (pinfunction "I11_5") (pintype "input"))
      (node (ref "E18") (pin "6") (pinfunction "I2_6") (pintype "input"))
      (node (ref "E23") (pin "5") (pinfunction "I11_5") (pintype "input"))
      (node (ref "E23") (pin "6") (pinfunction "I2_6") (pintype "input"))
      (node (ref "E24") (pin "5") (pinfunction "I11_5") (pintype "input"))
      (node (ref "E24") (pin "6") (pinfunction "I2_6") (pintype "input"))
      (node (ref "E36") (pin "5") (pinfunction "I11_5") (pintype "input"))
      (node (ref "E36") (pin "6") (pinfunction "I2_6") (pintype "input"))
      (node (ref "E5") (pin "4") (pinfunction "I1_4") (pintype "input"))
      (node (ref "E6") (pin "4") (pinfunction "I1_4") (pintype "input"))
      (node (ref "U$3") (pin "BV2") (pinfunction "1_BV2") (pintype "bidirectional"))
    )
    (net (code "69") (name "Net-(E19A-I11)") (class "Default")
      (node (ref "E19") (pin "5") (pinfunction "I11_5") (pintype "input"))
      (node (ref "E19") (pin "6") (pinfunction "I2_6") (pintype "input"))
      (node (ref "U$3") (pin "BD2") (pinfunction "1_BD2") (pintype "bidirectional"))
    )
    (net (code "70") (name "Net-(E19A-O)") (class "Default")
      (node (ref "E19") (pin "8") (pinfunction "O_8") (pintype "output"))
      (node (ref "U$3") (pin "BC1") (pinfunction "1_BC1") (pintype "bidirectional"))
    )
    (net (code "71") (name "Net-(E20E-A1)") (class "Default")
      (node (ref "E20") (pin "2") (pinfunction "A1_2") (pintype "input"))
      (node (ref "E29") (pin "1") (pinfunction "I0_1") (pintype "input"))
      (node (ref "E29") (pin "2") (pinfunction "I1_2") (pintype "input"))
      (node (ref "E35") (pin "8") (pinfunction "O_8") (pintype "output"))
    )
    (net (code "72") (name "Net-(E20E-A2)") (class "Default")
      (node (ref "E20") (pin "14") (pinfunction "A2_14") (pintype "input"))
      (node (ref "E30") (pin "1") (pinfunction "I0_1") (pintype "input"))
      (node (ref "E30") (pin "2") (pinfunction "I1_2") (pintype "input"))
      (node (ref "E36") (pin "8") (pinfunction "O_8") (pintype "output"))
    )
    (net (code "73") (name "Net-(E20E-B1)") (class "Default")
      (node (ref "E20") (pin "3") (pinfunction "B1_3") (pintype "input"))
      (node (ref "E27") (pin "1") (pinfunction "I0_1") (pintype "input"))
      (node (ref "E27") (pin "2") (pinfunction "I1_2") (pintype "input"))
      (node (ref "E33") (pin "8") (pinfunction "O_8") (pintype "output"))
    )
    (net (code "74") (name "Net-(E20E-B2)") (class "Default")
      (node (ref "E20") (pin "13") (pinfunction "B2_13") (pintype "input"))
      (node (ref "E28") (pin "1") (pinfunction "I0_1") (pintype "input"))
      (node (ref "E28") (pin "2") (pinfunction "I1_2") (pintype "input"))
      (node (ref "E34") (pin "8") (pinfunction "O_8") (pintype "output"))
    )
    (net (code "75") (name "Net-(E20E-C0)") (class "Default")
      (node (ref "E20") (pin "5") (pinfunction "C0_5") (pintype "input"))
      (node (ref "U$3") (pin "BE2") (pinfunction "1_BE2") (pintype "bidirectional"))
    )
    (net (code "76") (name "Net-(E20E-S1)") (class "Default")
      (node (ref "E20") (pin "1") (pinfunction "S1_1") (pintype "output"))
      (node (ref "E26") (pin "10") (pinfunction "I7_10") (pintype "input"))
      (node (ref "E32") (pin "3") (pinfunction "I6_3") (pintype "input"))
      (node (ref "U$3") (pin "BS1") (pinfunction "1_BS1") (pintype "bidirectional"))
    )
    (net (code "77") (name "Net-(E20E-S2)") (class "Default")
      (node (ref "E20") (pin "12") (pinfunction "S2_12") (pintype "output"))
      (node (ref "E26") (pin "3") (pinfunction "I6_3") (pintype "input"))
      (node (ref "E31") (pin "10") (pinfunction "I7_10") (pintype "input"))
      (node (ref "E32") (pin "13") (pinfunction "I3_13") (pintype "input"))
      (node (ref "U$3") (pin "BM1") (pinfunction "1_BM1") (pintype "bidirectional"))
    )
    (net (code "78") (name "Net-(E21A-I1)") (class "Default")
      (node (ref "E21") (pin "4") (pinfunction "I1_4") (pintype "input"))
      (node (ref "U$3") (pin "BF2") (pinfunction "1_BF2") (pintype "bidirectional"))
    )
    (net (code "79") (name "Net-(E21A-I4)") (class "Default")
      (node (ref "E21") (pin "1") (pinfunction "I4_1") (pintype "input"))
      (node (ref "E27") (pin "11") (pinfunction "O_11") (pintype "output"))
    )
    (net (code "80") (name "Net-(E21A-I5)") (class "Default")
      (node (ref "E21") (pin "2") (pinfunction "I5_2") (pintype "input"))
      (node (ref "E23") (pin "9") (pinfunction "I8_9") (pintype "input"))
      (node (ref "E29") (pin "10") (pinfunction "I1_10") (pintype "input"))
      (node (ref "E29") (pin "9") (pinfunction "I0_9") (pintype "input"))
      (node (ref "U$3") (pin "BV1") (pinfunction "1_BV1") (pintype "bidirectional"))
    )
    (net (code "81") (name "Net-(E21A-I8)") (class "Default")
      (node (ref "E21") (pin "9") (pinfunction "I8_9") (pintype "input"))
      (node (ref "E27") (pin "10") (pinfunction "I1_10") (pintype "input"))
      (node (ref "E27") (pin "9") (pinfunction "I0_9") (pintype "input"))
      (node (ref "U$3") (pin "BA1") (pinfunction "1_BA1") (pintype "bidirectional"))
    )
    (net (code "82") (name "Net-(E22A-I1)") (class "Default")
      (node (ref "E22") (pin "4") (pinfunction "I1_4") (pintype "input"))
      (node (ref "U$3") (pin "BE1") (pinfunction "1_BE1") (pintype "bidirectional"))
    )
    (net (code "83") (name "Net-(E22A-I4)") (class "Default")
      (node (ref "E22") (pin "1") (pinfunction "I4_1") (pintype "input"))
      (node (ref "E28") (pin "11") (pinfunction "O_11") (pintype "output"))
    )
    (net (code "84") (name "Net-(E22A-I5)") (class "Default")
      (node (ref "E22") (pin "2") (pinfunction "I5_2") (pintype "input"))
      (node (ref "E24") (pin "9") (pinfunction "I8_9") (pintype "input"))
      (node (ref "E30") (pin "10") (pinfunction "I1_10") (pintype "input"))
      (node (ref "E30") (pin "9") (pinfunction "I0_9") (pintype "input"))
      (node (ref "U$3") (pin "BH2") (pinfunction "1_BH2") (pintype "bidirectional"))
    )
    (net (code "85") (name "Net-(E22A-I8)") (class "Default")
      (node (ref "E22") (pin "9") (pinfunction "I8_9") (pintype "input"))
      (node (ref "E28") (pin "10") (pinfunction "I1_10") (pintype "input"))
      (node (ref "E28") (pin "9") (pinfunction "I0_9") (pintype "input"))
      (node (ref "U$3") (pin "BB1") (pinfunction "1_BB1") (pintype "bidirectional"))
    )
    (net (code "86") (name "Net-(E23A-I1)") (class "Default")
      (node (ref "E23") (pin "4") (pinfunction "I1_4") (pintype "input"))
      (node (ref "E29") (pin "8") (pinfunction "O_8") (pintype "output"))
    )
    (net (code "87") (name "Net-(E23A-I4)") (class "Default")
      (node (ref "E23") (pin "1") (pinfunction "I4_1") (pintype "input"))
      (node (ref "E29") (pin "11") (pinfunction "O_11") (pintype "output"))
    )
    (net (code "88") (name "Net-(E23A-I5)") (class "Default")
      (node (ref "E23") (pin "2") (pinfunction "I5_2") (pintype "input"))
      (node (ref "E27") (pin "8") (pinfunction "O_8") (pintype "output"))
    )
    (net (code "89") (name "Net-(E24A-I1)") (class "Default")
      (node (ref "E24") (pin "4") (pinfunction "I1_4") (pintype "input"))
      (node (ref "E30") (pin "8") (pinfunction "O_8") (pintype "output"))
    )
    (net (code "90") (name "Net-(E24A-I4)") (class "Default")
      (node (ref "E24") (pin "1") (pinfunction "I4_1") (pintype "input"))
      (node (ref "E30") (pin "11") (pinfunction "O_11") (pintype "output"))
    )
    (net (code "91") (name "Net-(E24A-I5)") (class "Default")
      (node (ref "E24") (pin "2") (pinfunction "I5_2") (pintype "input"))
      (node (ref "E28") (pin "8") (pinfunction "O_8") (pintype "output"))
    )
    (net (code "92") (name "Net-(E25A-I11)") (class "Default")
      (node (ref "E25") (pin "5") (pinfunction "I11_5") (pintype "input"))
      (node (ref "E25") (pin "6") (pinfunction "I2_6") (pintype "input"))
      (node (ref "U$3") (pin "BK2") (pinfunction "1_BK2") (pintype "bidirectional"))
    )
    (net (code "93") (name "Net-(E25A-O)") (class "Default")
      (node (ref "E25") (pin "8") (pinfunction "O_8") (pintype "output"))
      (node (ref "U$3") (pin "BH1") (pinfunction "1_BH1") (pintype "bidirectional"))
    )
    (net (code "94") (name "Net-(E26A-I11)") (class "Default")
      (node (ref "E26") (pin "5") (pinfunction "I11_5") (pintype "input"))
      (node (ref "E26") (pin "6") (pinfunction "I2_6") (pintype "input"))
      (node (ref "U$3") (pin "BF1") (pinfunction "1_BF1") (pintype "bidirectional"))
    )
    (net (code "95") (name "Net-(E26A-O)") (class "Default")
      (node (ref "E26") (pin "8") (pinfunction "O_8") (pintype "output"))
      (node (ref "U$3") (pin "AJ2") (pinfunction "1_AJ2") (pintype "bidirectional"))
    )
    (net (code "96") (name "Net-(E27A-O)") (class "Default")
      (node (ref "E27") (pin "3") (pinfunction "O_3") (pintype "output"))
      (node (ref "E33") (pin "1") (pinfunction "I4_1") (pintype "input"))
    )
    (net (code "97") (name "Net-(E27B-I0)") (class "Default")
      (node (ref "E27") (pin "4") (pinfunction "I0_4") (pintype "input"))
      (node (ref "E27") (pin "5") (pinfunction "I1_5") (pintype "input"))
      (node (ref "E33") (pin "9") (pinfunction "I8_9") (pintype "input"))
      (node (ref "U$3") (pin "BL2") (pinfunction "1_BL2") (pintype "bidirectional"))
    )
    (net (code "98") (name "Net-(E27B-O)") (class "Default")
      (node (ref "E27") (pin "6") (pinfunction "O_6") (pintype "output"))
      (node (ref "E35") (pin "2") (pinfunction "I5_2") (pintype "input"))
    )
    (net (code "99") (name "Net-(E28A-O)") (class "Default")
      (node (ref "E28") (pin "3") (pinfunction "O_3") (pintype "output"))
      (node (ref "E34") (pin "1") (pinfunction "I4_1") (pintype "input"))
    )
    (net (code "100") (name "Net-(E28B-I0)") (class "Default")
      (node (ref "E28") (pin "4") (pinfunction "I0_4") (pintype "input"))
      (node (ref "E28") (pin "5") (pinfunction "I1_5") (pintype "input"))
      (node (ref "E34") (pin "9") (pinfunction "I8_9") (pintype "input"))
      (node (ref "U$3") (pin "BK1") (pinfunction "1_BK1") (pintype "bidirectional"))
    )
    (net (code "101") (name "Net-(E28B-O)") (class "Default")
      (node (ref "E28") (pin "6") (pinfunction "O_6") (pintype "output"))
      (node (ref "E36") (pin "2") (pinfunction "I5_2") (pintype "input"))
    )
    (net (code "102") (name "Net-(E29A-O)") (class "Default")
      (node (ref "E29") (pin "3") (pinfunction "O_3") (pintype "output"))
      (node (ref "E35") (pin "1") (pinfunction "I4_1") (pintype "input"))
    )
    (net (code "103") (name "Net-(E29B-I0)") (class "Default")
      (node (ref "E29") (pin "4") (pinfunction "I0_4") (pintype "input"))
      (node (ref "E29") (pin "5") (pinfunction "I1_5") (pintype "input"))
      (node (ref "E33") (pin "2") (pinfunction "I5_2") (pintype "input"))
      (node (ref "E35") (pin "9") (pinfunction "I8_9") (pintype "input"))
      (node (ref "U$3") (pin "BU1") (pinfunction "1_BU1") (pintype "bidirectional"))
    )
    (net (code "104") (name "Net-(E29B-O)") (class "Default")
      (node (ref "E29") (pin "6") (pinfunction "O_6") (pintype "output"))
      (node (ref "E35") (pin "4") (pinfunction "I1_4") (pintype "input"))
    )
    (net (code "105") (name "Net-(E30A-O)") (class "Default")
      (node (ref "E30") (pin "3") (pinfunction "O_3") (pintype "output"))
      (node (ref "E36") (pin "1") (pinfunction "I4_1") (pintype "input"))
    )
    (net (code "106") (name "Net-(E30B-I0)") (class "Default")
      (node (ref "E30") (pin "4") (pinfunction "I0_4") (pintype "input"))
      (node (ref "E30") (pin "5") (pinfunction "I1_5") (pintype "input"))
      (node (ref "E34") (pin "2") (pinfunction "I5_2") (pintype "input"))
      (node (ref "E36") (pin "9") (pinfunction "I8_9") (pintype "input"))
      (node (ref "U$3") (pin "BT2") (pinfunction "1_BT2") (pintype "bidirectional"))
    )
    (net (code "107") (name "Net-(E30B-O)") (class "Default")
      (node (ref "E30") (pin "6") (pinfunction "O_6") (pintype "output"))
      (node (ref "E36") (pin "4") (pinfunction "I1_4") (pintype "input"))
    )
    (net (code "108") (name "Net-(E31A-I11)") (class "Default")
      (node (ref "E31") (pin "5") (pinfunction "I11_5") (pintype "input"))
      (node (ref "E31") (pin "6") (pinfunction "I2_6") (pintype "input"))
      (node (ref "U$3") (pin "BP1") (pinfunction "1_BP1") (pintype "bidirectional"))
    )
    (net (code "109") (name "Net-(E31A-O)") (class "Default")
      (node (ref "E31") (pin "8") (pinfunction "O_8") (pintype "output"))
      (node (ref "U$3") (pin "BN1") (pinfunction "1_BN1") (pintype "bidirectional"))
    )
    (net (code "110") (name "Net-(E32A-I7)") (class "Default")
      (node (ref "E32") (pin "10") (pinfunction "I7_10") (pintype "input"))
      (node (ref "U$3") (pin "BJ2") (pinfunction "1_BJ2") (pintype "bidirectional"))
    )
    (net (code "111") (name "Net-(E32A-I11)") (class "Default")
      (node (ref "E32") (pin "5") (pinfunction "I11_5") (pintype "input"))
      (node (ref "E32") (pin "6") (pinfunction "I2_6") (pintype "input"))
      (node (ref "U$3") (pin "BR1") (pinfunction "1_BR1") (pintype "bidirectional"))
    )
    (net (code "112") (name "Net-(E32A-O)") (class "Default")
      (node (ref "E32") (pin "8") (pinfunction "O_8") (pintype "output"))
      (node (ref "U$3") (pin "BM2") (pinfunction "1_BM2") (pintype "bidirectional"))
    )
    (net (code "113") (name "Net-(E33A-I1)") (class "Default")
      (node (ref "E3") (pin "4") (pinfunction "I1_4") (pintype "input"))
      (node (ref "E3") (pin "5") (pinfunction "I11_5") (pintype "input"))
      (node (ref "E3") (pin "6") (pinfunction "I2_6") (pintype "input"))
      (node (ref "E33") (pin "4") (pinfunction "I1_4") (pintype "input"))
      (node (ref "E33") (pin "5") (pinfunction "I11_5") (pintype "input"))
      (node (ref "E33") (pin "6") (pinfunction "I2_6") (pintype "input"))
      (node (ref "E34") (pin "4") (pinfunction "I1_4") (pintype "input"))
      (node (ref "E34") (pin "5") (pinfunction "I11_5") (pintype "input"))
      (node (ref "E34") (pin "6") (pinfunction "I2_6") (pintype "input"))
      (node (ref "E4") (pin "4") (pinfunction "I1_4") (pintype "input"))
      (node (ref "E4") (pin "5") (pinfunction "I11_5") (pintype "input"))
      (node (ref "E4") (pin "6") (pinfunction "I2_6") (pintype "input"))
      (node (ref "U$3") (pin "BP2") (pinfunction "1_BP2") (pintype "bidirectional"))
    )
    (net (code "114") (name "Net-(E35A-I7)") (class "Default")
      (node (ref "E35") (pin "10") (pinfunction "I7_10") (pintype "input"))
      (node (ref "U$3") (pin "BL1") (pinfunction "1_BL1") (pintype "bidirectional"))
    )
    (net (code "115") (name "Net-(E35A-I11)") (class "Default")
      (node (ref "E35") (pin "5") (pinfunction "I11_5") (pintype "input"))
      (node (ref "E35") (pin "6") (pinfunction "I2_6") (pintype "input"))
      (node (ref "U$3") (pin "BU2") (pinfunction "1_BU2") (pintype "bidirectional"))
    )
    (net (code "116") (name "VCC") (class "Default")
      (node (ref "C1") (pin "1") (pinfunction "1_1") (pintype "passive"))
      (node (ref "C10") (pin "1") (pinfunction "1_1") (pintype "passive"))
      (node (ref "C11") (pin "1") (pinfunction "1_1") (pintype "passive"))
      (node (ref "C12") (pin "1") (pinfunction "1_1") (pintype "passive"))
      (node (ref "C13") (pin "1") (pinfunction "1_1") (pintype "passive"))
      (node (ref "C14") (pin "1") (pinfunction "1_1") (pintype "passive"))
      (node (ref "C15") (pin "1") (pinfunction "1_1") (pintype "passive"))
      (node (ref "C16") (pin "1") (pinfunction "1_1") (pintype "passive"))
      (node (ref "C17") (pin "1") (pinfunction "1_1") (pintype "passive"))
      (node (ref "C18") (pin "1") (pinfunction "1_1") (pintype "passive"))
      (node (ref "C19") (pin "1") (pinfunction "1_1") (pintype "passive"))
      (node (ref "C2") (pin "1") (pinfunction "1_1") (pintype "passive"))
      (node (ref "C20") (pin "1") (pinfunction "1_1") (pintype "passive"))
      (node (ref "C21") (pin "1") (pinfunction "1_1") (pintype "passive"))
      (node (ref "C22") (pin "1") (pinfunction "1_1") (pintype "passive"))
      (node (ref "C23") (pin "1") (pinfunction "1_1") (pintype "passive"))
      (node (ref "C24") (pin "1") (pinfunction "1_1") (pintype "passive"))
      (node (ref "C25") (pin "1") (pinfunction "1_1") (pintype "passive"))
      (node (ref "C26") (pin "1") (pinfunction "1_1") (pintype "passive"))
      (node (ref "C27") (pin "1") (pinfunction "1_1") (pintype "passive"))
      (node (ref "C28") (pin "1") (pinfunction "1_1") (pintype "passive"))
      (node (ref "C29") (pin "1") (pinfunction "1_1") (pintype "passive"))
      (node (ref "C3") (pin "1") (pinfunction "1_1") (pintype "passive"))
      (node (ref "C30") (pin "1") (pinfunction "1_1") (pintype "passive"))
      (node (ref "C31") (pin "1") (pinfunction "1_1") (pintype "passive"))
      (node (ref "C32") (pin "1") (pinfunction "1_1") (pintype "passive"))
      (node (ref "C33") (pin "1") (pinfunction "1_1") (pintype "passive"))
      (node (ref "C34") (pin "1") (pinfunction "1_1") (pintype "passive"))
      (node (ref "C35") (pin "1") (pinfunction "1_1") (pintype "passive"))
      (node (ref "C36") (pin "1") (pinfunction "1_1") (pintype "passive"))
      (node (ref "C37") (pin "+") (pinfunction "+_+") (pintype "passive"))
      (node (ref "C38") (pin "+") (pinfunction "+_+") (pintype "passive"))
      (node (ref "C4") (pin "1") (pinfunction "1_1") (pintype "passive"))
      (node (ref "C5") (pin "1") (pinfunction "1_1") (pintype "passive"))
      (node (ref "C6") (pin "1") (pinfunction "1_1") (pintype "passive"))
      (node (ref "C7") (pin "1") (pinfunction "1_1") (pintype "passive"))
      (node (ref "C8") (pin "1") (pinfunction "1_1") (pintype "passive"))
      (node (ref "C9") (pin "1") (pinfunction "1_1") (pintype "passive"))
      (node (ref "U$3") (pin "AA2") (pinfunction "1_AA2") (pintype "bidirectional"))
      (node (ref "U$3") (pin "BA2") (pinfunction "1_BA2") (pintype "bidirectional"))
    )
    (net (code "117") (name "unconnected-(E1A-I9-Pad12)") (class "Default")
      (node (ref "E1") (pin "12") (pinfunction "I9_12") (pintype "passive"))
    )
    (net (code "118") (name "unconnected-(E1A-I10-Pad11)") (class "Default")
      (node (ref "E1") (pin "11") (pinfunction "I10_11") (pintype "passive"))
    )
    (net (code "119") (name "unconnected-(E3A-I9-Pad12)") (class "Default")
      (node (ref "E3") (pin "12") (pinfunction "I9_12") (pintype "passive"))
    )
    (net (code "120") (name "unconnected-(E3A-I10-Pad11)") (class "Default")
      (node (ref "E3") (pin "11") (pinfunction "I10_11") (pintype "passive"))
    )
    (net (code "121") (name "unconnected-(E4A-I9-Pad12)") (class "Default")
      (node (ref "E4") (pin "12") (pinfunction "I9_12") (pintype "passive"))
    )
    (net (code "122") (name "unconnected-(E4A-I10-Pad11)") (class "Default")
      (node (ref "E4") (pin "11") (pinfunction "I10_11") (pintype "passive"))
    )
    (net (code "123") (name "unconnected-(E5A-I9-Pad12)") (class "Default")
      (node (ref "E5") (pin "12") (pinfunction "I9_12") (pintype "passive"))
    )
    (net (code "124") (name "unconnected-(E5A-I10-Pad11)") (class "Default")
      (node (ref "E5") (pin "11") (pinfunction "I10_11") (pintype "passive"))
    )
    (net (code "125") (name "unconnected-(E6A-I9-Pad12)") (class "Default")
      (node (ref "E6") (pin "12") (pinfunction "I9_12") (pintype "passive"))
    )
    (net (code "126") (name "unconnected-(E6A-I10-Pad11)") (class "Default")
      (node (ref "E6") (pin "11") (pinfunction "I10_11") (pintype "passive"))
    )
    (net (code "127") (name "unconnected-(E7A-I9-Pad12)") (class "Default")
      (node (ref "E7") (pin "12") (pinfunction "I9_12") (pintype "passive"))
    )
    (net (code "128") (name "unconnected-(E7A-I10-Pad11)") (class "Default")
      (node (ref "E7") (pin "11") (pinfunction "I10_11") (pintype "passive"))
    )
    (net (code "129") (name "unconnected-(E13A-I9-Pad12)") (class "Default")
      (node (ref "E13") (pin "12") (pinfunction "I9_12") (pintype "passive"))
    )
    (net (code "130") (name "unconnected-(E13A-I10-Pad11)") (class "Default")
      (node (ref "E13") (pin "11") (pinfunction "I10_11") (pintype "passive"))
    )
    (net (code "131") (name "unconnected-(E15A-I9-Pad12)") (class "Default")
      (node (ref "E15") (pin "12") (pinfunction "I9_12") (pintype "passive"))
    )
    (net (code "132") (name "unconnected-(E15A-I10-Pad11)") (class "Default")
      (node (ref "E15") (pin "11") (pinfunction "I10_11") (pintype "passive"))
    )
    (net (code "133") (name "unconnected-(E16A-I9-Pad12)") (class "Default")
      (node (ref "E16") (pin "12") (pinfunction "I9_12") (pintype "passive"))
    )
    (net (code "134") (name "unconnected-(E16A-I10-Pad11)") (class "Default")
      (node (ref "E16") (pin "11") (pinfunction "I10_11") (pintype "passive"))
    )
    (net (code "135") (name "unconnected-(E17A-I9-Pad12)") (class "Default")
      (node (ref "E17") (pin "12") (pinfunction "I9_12") (pintype "passive"))
    )
    (net (code "136") (name "unconnected-(E17A-I10-Pad11)") (class "Default")
      (node (ref "E17") (pin "11") (pinfunction "I10_11") (pintype "passive"))
    )
    (net (code "137") (name "unconnected-(E18A-I9-Pad12)") (class "Default")
      (node (ref "E18") (pin "12") (pinfunction "I9_12") (pintype "passive"))
    )
    (net (code "138") (name "unconnected-(E18A-I10-Pad11)") (class "Default")
      (node (ref "E18") (pin "11") (pinfunction "I10_11") (pintype "passive"))
    )
    (net (code "139") (name "unconnected-(E19A-I9-Pad12)") (class "Default")
      (node (ref "E19") (pin "12") (pinfunction "I9_12") (pintype "passive"))
    )
    (net (code "140") (name "unconnected-(E19A-I10-Pad11)") (class "Default")
      (node (ref "E19") (pin "11") (pinfunction "I10_11") (pintype "passive"))
    )
    (net (code "141") (name "unconnected-(E21A-I9-Pad12)") (class "Default")
      (node (ref "E21") (pin "12") (pinfunction "I9_12") (pintype "passive"))
    )
    (net (code "142") (name "unconnected-(E21A-I10-Pad11)") (class "Default")
      (node (ref "E21") (pin "11") (pinfunction "I10_11") (pintype "passive"))
    )
    (net (code "143") (name "unconnected-(E22A-I9-Pad12)") (class "Default")
      (node (ref "E22") (pin "12") (pinfunction "I9_12") (pintype "passive"))
    )
    (net (code "144") (name "unconnected-(E22A-I10-Pad11)") (class "Default")
      (node (ref "E22") (pin "11") (pinfunction "I10_11") (pintype "passive"))
    )
    (net (code "145") (name "unconnected-(E23A-I9-Pad12)") (class "Default")
      (node (ref "E23") (pin "12") (pinfunction "I9_12") (pintype "passive"))
    )
    (net (code "146") (name "unconnected-(E23A-I10-Pad11)") (class "Default")
      (node (ref "E23") (pin "11") (pinfunction "I10_11") (pintype "passive"))
    )
    (net (code "147") (name "unconnected-(E24A-I9-Pad12)") (class "Default")
      (node (ref "E24") (pin "12") (pinfunction "I9_12") (pintype "passive"))
    )
    (net (code "148") (name "unconnected-(E24A-I10-Pad11)") (class "Default")
      (node (ref "E24") (pin "11") (pinfunction "I10_11") (pintype "passive"))
    )
    (net (code "149") (name "unconnected-(E25A-I9-Pad12)") (class "Default")
      (node (ref "E25") (pin "12") (pinfunction "I9_12") (pintype "passive"))
    )
    (net (code "150") (name "unconnected-(E25A-I10-Pad11)") (class "Default")
      (node (ref "E25") (pin "11") (pinfunction "I10_11") (pintype "passive"))
    )
    (net (code "151") (name "unconnected-(E26A-I9-Pad12)") (class "Default")
      (node (ref "E26") (pin "12") (pinfunction "I9_12") (pintype "passive"))
    )
    (net (code "152") (name "unconnected-(E26A-I10-Pad11)") (class "Default")
      (node (ref "E26") (pin "11") (pinfunction "I10_11") (pintype "passive"))
    )
    (net (code "153") (name "unconnected-(E31A-I9-Pad12)") (class "Default")
      (node (ref "E31") (pin "12") (pinfunction "I9_12") (pintype "passive"))
    )
    (net (code "154") (name "unconnected-(E31A-I10-Pad11)") (class "Default")
      (node (ref "E31") (pin "11") (pinfunction "I10_11") (pintype "passive"))
    )
    (net (code "155") (name "unconnected-(E32A-I9-Pad12)") (class "Default")
      (node (ref "E32") (pin "12") (pinfunction "I9_12") (pintype "passive"))
    )
    (net (code "156") (name "unconnected-(E32A-I10-Pad11)") (class "Default")
      (node (ref "E32") (pin "11") (pinfunction "I10_11") (pintype "passive"))
    )
    (net (code "157") (name "unconnected-(E33A-I9-Pad12)") (class "Default")
      (node (ref "E33") (pin "12") (pinfunction "I9_12") (pintype "passive"))
    )
    (net (code "158") (name "unconnected-(E33A-I10-Pad11)") (class "Default")
      (node (ref "E33") (pin "11") (pinfunction "I10_11") (pintype "passive"))
    )
    (net (code "159") (name "unconnected-(E34A-I9-Pad12)") (class "Default")
      (node (ref "E34") (pin "12") (pinfunction "I9_12") (pintype "passive"))
    )
    (net (code "160") (name "unconnected-(E34A-I10-Pad11)") (class "Default")
      (node (ref "E34") (pin "11") (pinfunction "I10_11") (pintype "passive"))
    )
    (net (code "161") (name "unconnected-(E35A-I9-Pad12)") (class "Default")
      (node (ref "E35") (pin "12") (pinfunction "I9_12") (pintype "passive"))
    )
    (net (code "162") (name "unconnected-(E35A-I10-Pad11)") (class "Default")
      (node (ref "E35") (pin "11") (pinfunction "I10_11") (pintype "passive"))
    )
    (net (code "163") (name "unconnected-(E36A-I9-Pad12)") (class "Default")
      (node (ref "E36") (pin "12") (pinfunction "I9_12") (pintype "passive"))
    )
    (net (code "164") (name "unconnected-(E36A-I10-Pad11)") (class "Default")
      (node (ref "E36") (pin "11") (pinfunction "I10_11") (pintype "passive"))
    )
  )
)
